# Connectors.net
KiCad netlist of a schematic drawn in Altium Designer
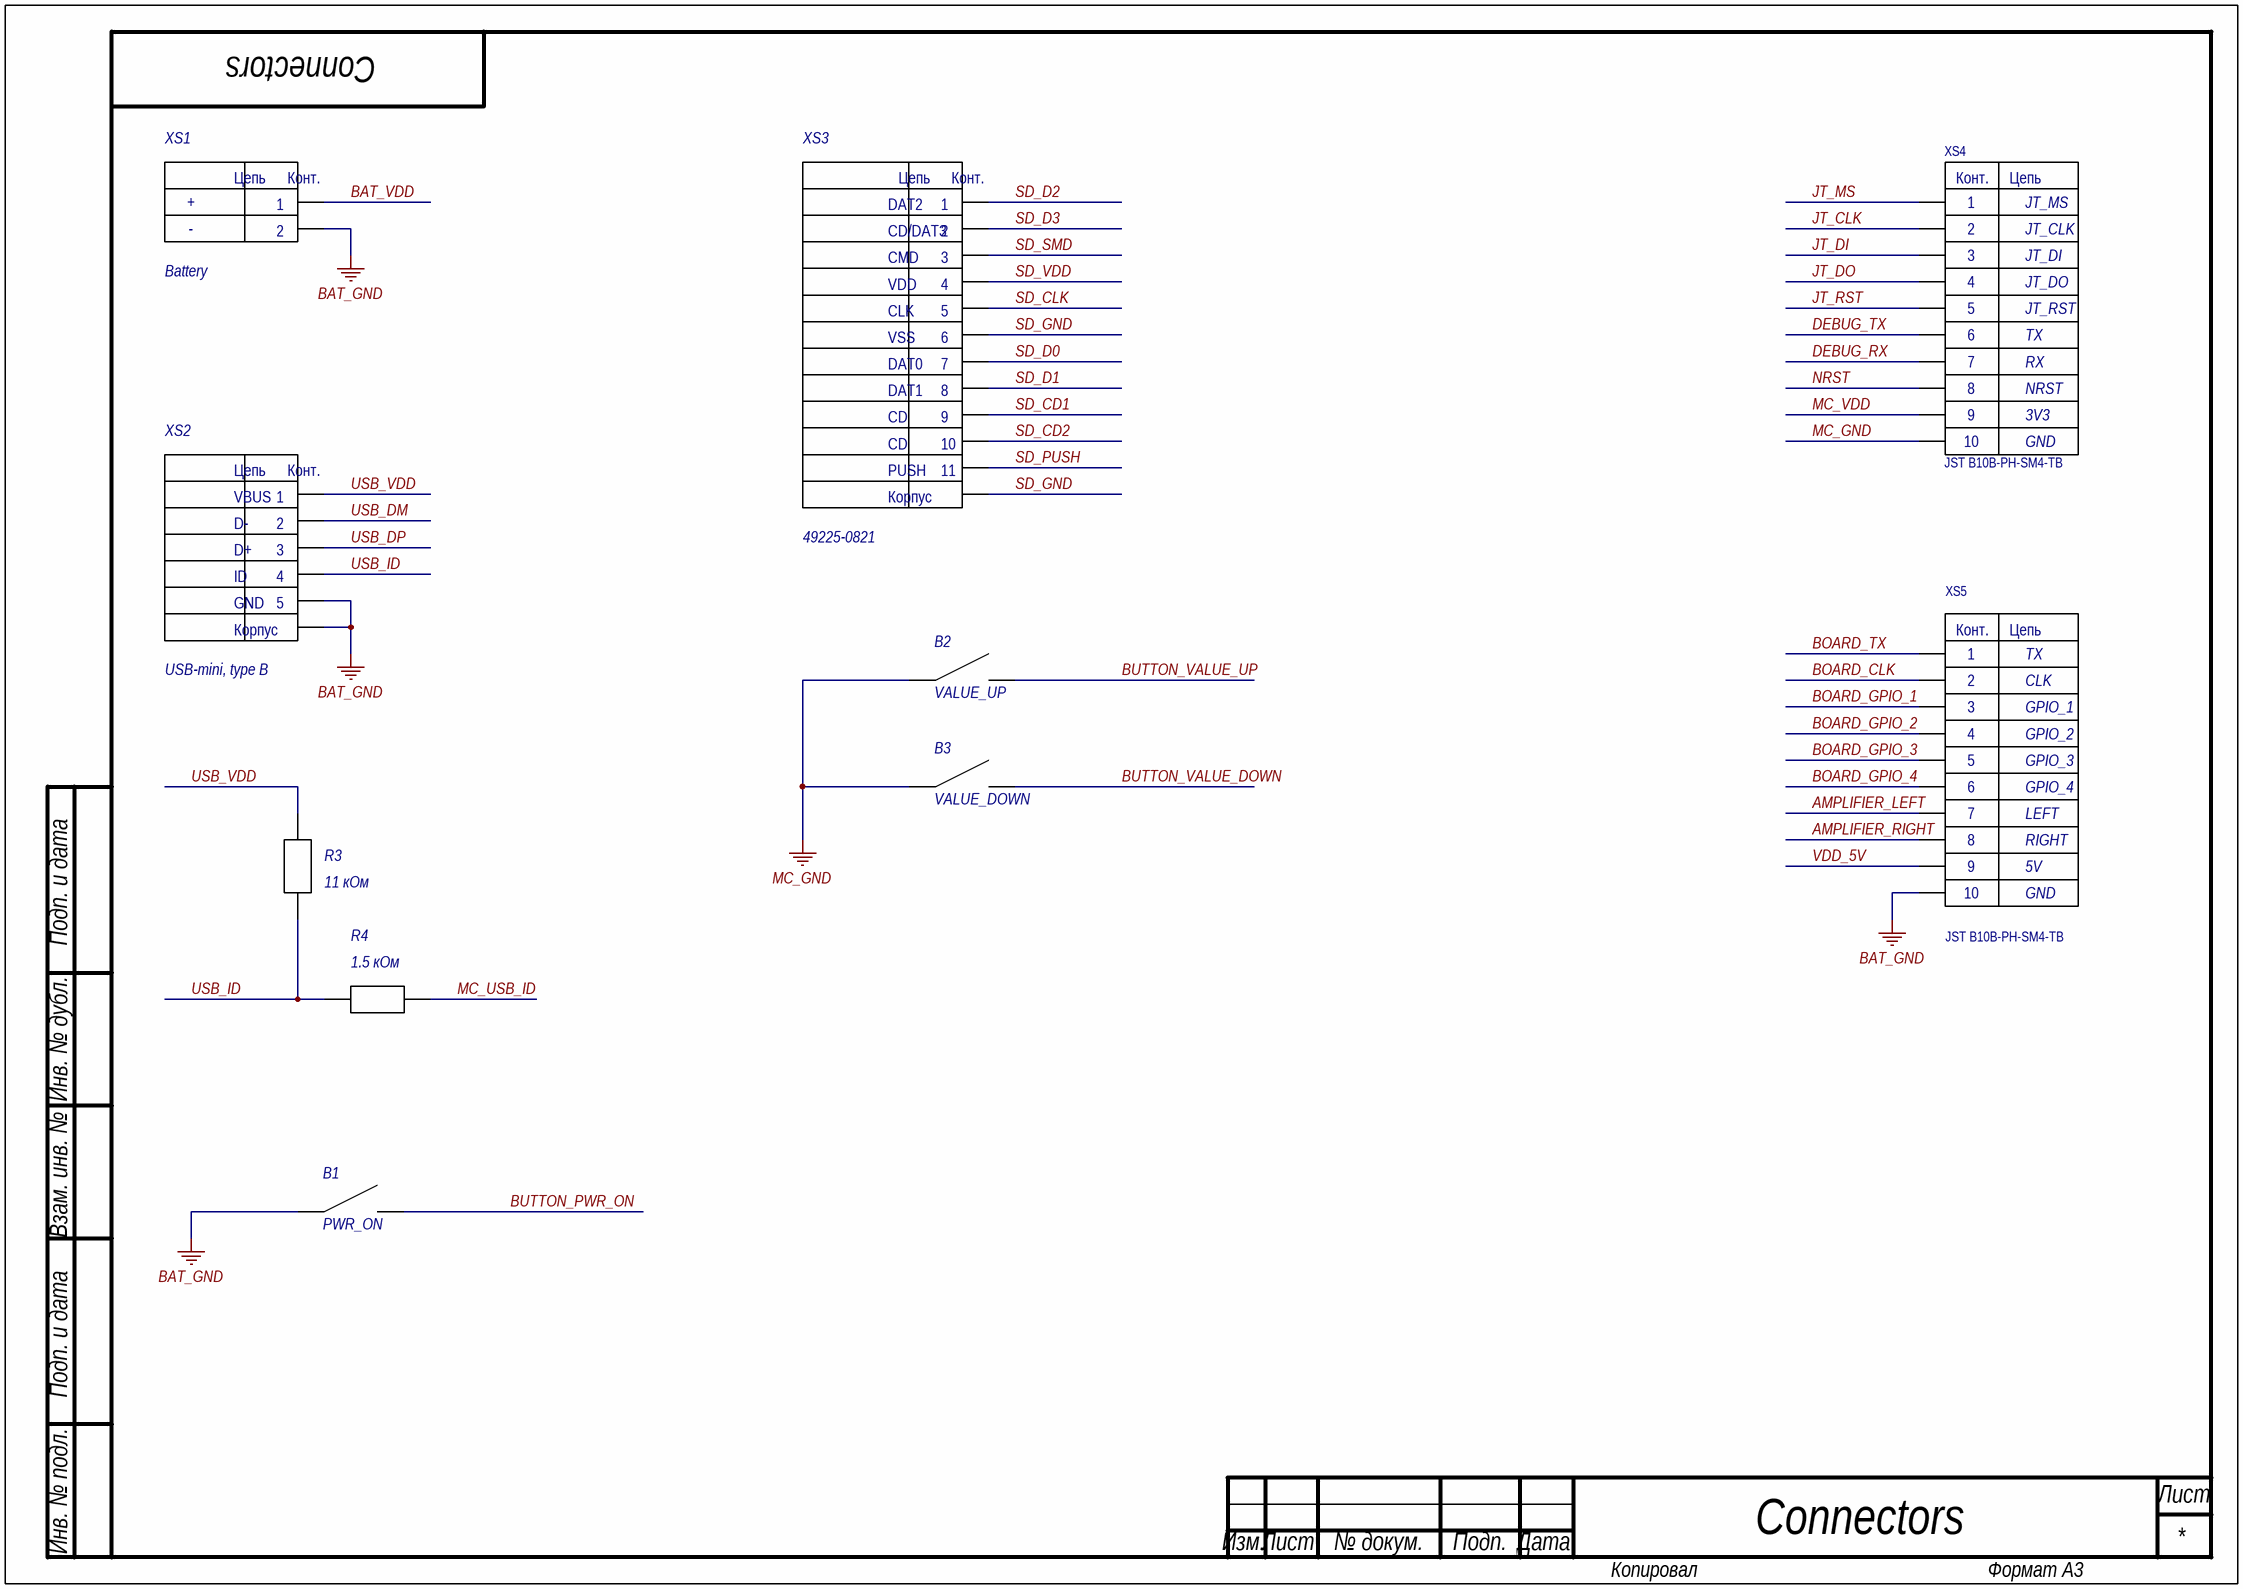
[diagram p0: Connectors.SchDoc]

(export (version "E")
  (design (tool "Eeschema 10.0.6"))
  (components
    (comp (ref "B1")
      (value "PWR_ON")
      (footprint "TACT SKHH Horizontal Switch")
      (libsource (lib "my_lib") (part "BUTTON"))
    )
    (comp (ref "B2")
      (value "VALUE_UP")
      (footprint "TACT SKHH Horizontal Switch")
      (libsource (lib "my_lib") (part "BUTTON"))
    )
    (comp (ref "B3")
      (value "VALUE_DOWN")
      (footprint "TACT SKHH Horizontal Switch")
      (libsource (lib "my_lib") (part "BUTTON"))
    )
    (comp (ref "R3") (value "11 кОм") (footprint "RES 0402") (libsource (lib "my_lib") (part "RES 0402")))
    (comp (ref "R4") (value "1.5 кОм") (footprint "RES 0402") (libsource (lib "my_lib") (part "RES 0402")))
    (comp (ref "XS1")
      (value "Battery")
      (footprint "JST B2B-PH-SM4-TB")
      (libsource (lib "my_lib") (part "JST B2B-PH-SM4-TB"))
    )
    (comp (ref "XS2")
      (value "USB-mini, type B")
      (footprint "USB_mini_B")
      (description "USB-mini-B connector")
      (fields (field (name "MANUFACTURER") "NONAME"))
      (libsource (lib "my_lib") (part "USB-mini_B"))
    )
    (comp (ref "XS3")
      (value "49225-0821")
      (footprint "MOLEX 49225-0821")
      (description "MOLEX MicroSD connector")
      (fields (field (name "MANUFACTURER") "Molex"))
      (libsource (lib "my_lib") (part "49225-0821"))
    )
    (comp (ref "XS4")
      (value "JST B10B-PH-SM4-TB")
      (footprint "B10B-PH-SM4-TB")
      (description "PLS connector")
      (fields (field (name "MANUFACTURER") "NONAME"))
      (libsource (lib "my_lib") (part "JST B10B-PH-SM4-TB"))
    )
    (comp (ref "XS5")
      (value "JST B10B-PH-SM4-TB")
      (footprint "B10B-PH-SM4-TB")
      (description "PLS connector")
      (fields (field (name "MANUFACTURER") "NONAME"))
      (libsource (lib "my_lib") (part "JST B10B-PH-SM4-TB"))
    )
  )
  (nets
    (net (code "1") (name "/AMPLIFIER_LEFT") (class "Default")
      (node (ref "XS5") (pin "7") (pinfunction "7_7") (pintype "passive"))
    )
    (net (code "2") (name "/AMPLIFIER_RIGHT") (class "Default")
      (node (ref "XS5") (pin "8") (pinfunction "8_8") (pintype "passive"))
    )
    (net (code "3") (name "/BAT_VDD") (class "Default")
      (node (ref "XS1") (pin "1") (pinfunction "1_1") (pintype "passive"))
    )
    (net (code "4") (name "/BOARD_CLK") (class "Default")
      (node (ref "XS5") (pin "2") (pinfunction "2_2") (pintype "passive"))
    )
    (net (code "5") (name "/BOARD_GPIO_1") (class "Default")
      (node (ref "XS5") (pin "3") (pinfunction "3_3") (pintype "passive"))
    )
    (net (code "6") (name "/BOARD_GPIO_2") (class "Default")
      (node (ref "XS5") (pin "4") (pinfunction "4_4") (pintype "passive"))
    )
    (net (code "7") (name "/BOARD_GPIO_3") (class "Default")
      (node (ref "XS5") (pin "5") (pinfunction "5_5") (pintype "passive"))
    )
    (net (code "8") (name "/BOARD_GPIO_4") (class "Default")
      (node (ref "XS5") (pin "6") (pinfunction "6_6") (pintype "passive"))
    )
    (net (code "9") (name "/BOARD_TX") (class "Default")
      (node (ref "XS5") (pin "1") (pinfunction "1_1") (pintype "passive"))
    )
    (net (code "10") (name "/BUTTON_PWR_ON") (class "Default")
      (node (ref "B1") (pin "2") (pinfunction "2_2") (pintype "passive"))
    )
    (net (code "11") (name "/BUTTON_VALUE_DOWN") (class "Default")
      (node (ref "B3") (pin "2") (pinfunction "2_2") (pintype "passive"))
    )
    (net (code "12") (name "/BUTTON_VALUE_UP") (class "Default")
      (node (ref "B2") (pin "2") (pinfunction "2_2") (pintype "passive"))
    )
    (net (code "13") (name "/DEBUG_RX") (class "Default")
      (node (ref "XS4") (pin "7") (pinfunction "7_7") (pintype "passive"))
    )
    (net (code "14") (name "/DEBUG_TX") (class "Default")
      (node (ref "XS4") (pin "6") (pinfunction "6_6") (pintype "passive"))
    )
    (net (code "15") (name "/JT_CLK") (class "Default")
      (node (ref "XS4") (pin "2") (pinfunction "2_2") (pintype "passive"))
    )
    (net (code "16") (name "/JT_DI") (class "Default")
      (node (ref "XS4") (pin "3") (pinfunction "3_3") (pintype "passive"))
    )
    (net (code "17") (name "/JT_DO") (class "Default")
      (node (ref "XS4") (pin "4") (pinfunction "4_4") (pintype "passive"))
    )
    (net (code "18") (name "/JT_MS") (class "Default")
      (node (ref "XS4") (pin "1") (pinfunction "1_1") (pintype "passive"))
    )
    (net (code "19") (name "/JT_RST") (class "Default")
      (node (ref "XS4") (pin "5") (pinfunction "5_5") (pintype "passive"))
    )
    (net (code "20") (name "/MC_USB_ID") (class "Default")
      (node (ref "R4") (pin "1") (pinfunction "1_1") (pintype "passive"))
    )
    (net (code "21") (name "/MC_VDD") (class "Default")
      (node (ref "XS4") (pin "9") (pinfunction "9_9") (pintype "passive"))
    )
    (net (code "22") (name "/NRST") (class "Default")
      (node (ref "XS4") (pin "8") (pinfunction "8_8") (pintype "passive"))
    )
    (net (code "23") (name "/SD_CD1") (class "Default")
      (node (ref "XS3") (pin "9") (pinfunction "9_9") (pintype "passive"))
    )
    (net (code "24") (name "/SD_CD2") (class "Default")
      (node (ref "XS3") (pin "10") (pinfunction "10_10") (pintype "passive"))
    )
    (net (code "25") (name "/SD_CLK") (class "Default")
      (node (ref "XS3") (pin "5") (pinfunction "5_5") (pintype "passive"))
    )
    (net (code "26") (name "/SD_D0") (class "Default")
      (node (ref "XS3") (pin "7") (pinfunction "7_7") (pintype "passive"))
    )
    (net (code "27") (name "/SD_D1") (class "Default")
      (node (ref "XS3") (pin "8") (pinfunction "8_8") (pintype "passive"))
    )
    (net (code "28") (name "/SD_D2") (class "Default")
      (node (ref "XS3") (pin "1") (pinfunction "1_1") (pintype "passive"))
    )
    (net (code "29") (name "/SD_D3") (class "Default")
      (node (ref "XS3") (pin "2") (pinfunction "2_2") (pintype "passive"))
    )
    (net (code "30") (name "/SD_GND") (class "Default")
      (node (ref "XS3") (pin "0") (pinfunction "0_0") (pintype "passive"))
      (node (ref "XS3") (pin "6") (pinfunction "6_6") (pintype "passive"))
    )
    (net (code "31") (name "/SD_PUSH") (class "Default")
      (node (ref "XS3") (pin "11") (pinfunction "11_11") (pintype "passive"))
    )
    (net (code "32") (name "/SD_SMD") (class "Default")
      (node (ref "XS3") (pin "3") (pinfunction "3_3") (pintype "passive"))
    )
    (net (code "33") (name "/SD_VDD") (class "Default")
      (node (ref "XS3") (pin "4") (pinfunction "4_4") (pintype "passive"))
    )
    (net (code "34") (name "/USB_DM") (class "Default")
      (node (ref "XS2") (pin "2") (pinfunction "D-_2") (pintype "passive"))
    )
    (net (code "35") (name "/USB_DP") (class "Default")
      (node (ref "XS2") (pin "3") (pinfunction "D+_3") (pintype "passive"))
    )
    (net (code "36") (name "/USB_ID") (class "Default")
      (node (ref "R3") (pin "1") (pinfunction "1_1") (pintype "passive"))
      (node (ref "R4") (pin "2") (pinfunction "2_2") (pintype "passive"))
      (node (ref "XS2") (pin "4") (pinfunction "CASE_4") (pintype "passive"))
    )
    (net (code "37") (name "/USB_VDD") (class "Default")
      (node (ref "R3") (pin "2") (pinfunction "2_2") (pintype "passive"))
      (node (ref "XS2") (pin "1") (pinfunction "VBUS_1") (pintype "passive"))
    )
    (net (code "38") (name "/VDD_5V") (class "Default")
      (node (ref "XS5") (pin "9") (pinfunction "9_9") (pintype "passive"))
    )
    (net (code "39") (name "BAT_GND") (class "Default")
      (node (ref "B1") (pin "1") (pinfunction "1_1") (pintype "passive"))
      (node (ref "XS1") (pin "2") (pinfunction "2_2") (pintype "passive"))
      (node (ref "XS2") (pin "0") (pinfunction "0_0") (pintype "passive"))
      (node (ref "XS2") (pin "5") (pinfunction "GND_5") (pintype "passive"))
      (node (ref "XS5") (pin "10") (pinfunction "10_10") (pintype "passive"))
    )
    (net (code "40") (name "MC_GND") (class "Default")
      (node (ref "B2") (pin "1") (pinfunction "1_1") (pintype "passive"))
      (node (ref "B3") (pin "1") (pinfunction "1_1") (pintype "passive"))
      (node (ref "XS4") (pin "10") (pinfunction "10_10") (pintype "passive"))
    )
  )
)
